# BadgeBoard.net
KiCad netlist of a schematic drawn in EAGLE
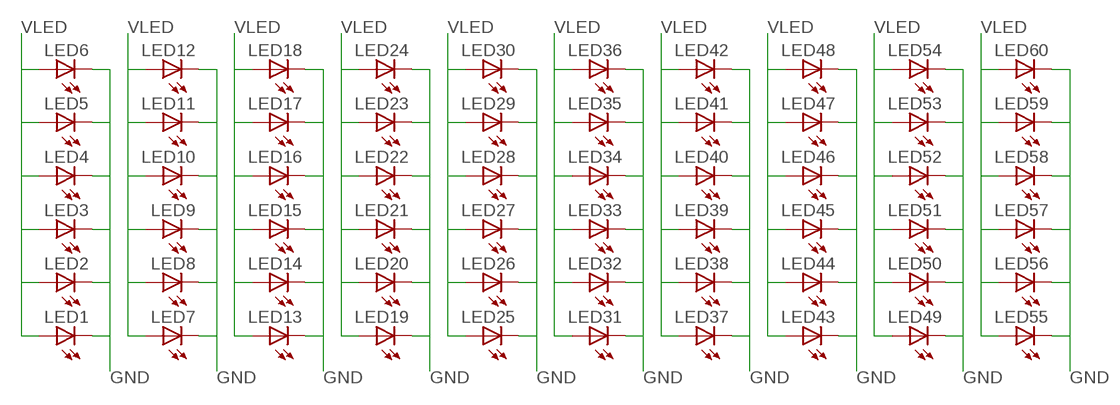
[diagram p0: schematic, sheet 1]

(export (version "E")
  (design (tool "Eeschema 10.0.6"))
  (components
    (comp (ref "LED1")
      (value "LED3MM")
      (footprint "eagle-import:LED3MM")
      (libsource (lib "eagle-import") (part "LED3MM"))
    )
    (comp (ref "LED2")
      (value "LED3MM")
      (footprint "eagle-import:LED3MM")
      (libsource (lib "eagle-import") (part "LED3MM"))
    )
    (comp (ref "LED3")
      (value "LED3MM")
      (footprint "eagle-import:LED3MM")
      (libsource (lib "eagle-import") (part "LED3MM"))
    )
    (comp (ref "LED4")
      (value "LED3MM")
      (footprint "eagle-import:LED3MM")
      (libsource (lib "eagle-import") (part "LED3MM"))
    )
    (comp (ref "LED5")
      (value "LED3MM")
      (footprint "eagle-import:LED3MM")
      (libsource (lib "eagle-import") (part "LED3MM"))
    )
    (comp (ref "LED6")
      (value "LED3MM")
      (footprint "eagle-import:LED3MM")
      (libsource (lib "eagle-import") (part "LED3MM"))
    )
    (comp (ref "LED7")
      (value "LED3MM")
      (footprint "eagle-import:LED3MM")
      (libsource (lib "eagle-import") (part "LED3MM"))
    )
    (comp (ref "LED8")
      (value "LED3MM")
      (footprint "eagle-import:LED3MM")
      (libsource (lib "eagle-import") (part "LED3MM"))
    )
    (comp (ref "LED9")
      (value "LED3MM")
      (footprint "eagle-import:LED3MM")
      (libsource (lib "eagle-import") (part "LED3MM"))
    )
    (comp (ref "LED10")
      (value "LED3MM")
      (footprint "eagle-import:LED3MM")
      (libsource (lib "eagle-import") (part "LED3MM"))
    )
    (comp (ref "LED11")
      (value "LED3MM")
      (footprint "eagle-import:LED3MM")
      (libsource (lib "eagle-import") (part "LED3MM"))
    )
    (comp (ref "LED12")
      (value "LED3MM")
      (footprint "eagle-import:LED3MM")
      (libsource (lib "eagle-import") (part "LED3MM"))
    )
    (comp (ref "LED13")
      (value "LED3MM")
      (footprint "eagle-import:LED3MM")
      (libsource (lib "eagle-import") (part "LED3MM"))
    )
    (comp (ref "LED14")
      (value "LED3MM")
      (footprint "eagle-import:LED3MM")
      (libsource (lib "eagle-import") (part "LED3MM"))
    )
    (comp (ref "LED15")
      (value "LED3MM")
      (footprint "eagle-import:LED3MM")
      (libsource (lib "eagle-import") (part "LED3MM"))
    )
    (comp (ref "LED16")
      (value "LED3MM")
      (footprint "eagle-import:LED3MM")
      (libsource (lib "eagle-import") (part "LED3MM"))
    )
    (comp (ref "LED17")
      (value "LED3MM")
      (footprint "eagle-import:LED3MM")
      (libsource (lib "eagle-import") (part "LED3MM"))
    )
    (comp (ref "LED18")
      (value "LED3MM")
      (footprint "eagle-import:LED3MM")
      (libsource (lib "eagle-import") (part "LED3MM"))
    )
    (comp (ref "LED19")
      (value "LED3MM")
      (footprint "eagle-import:LED3MM")
      (libsource (lib "eagle-import") (part "LED3MM"))
    )
    (comp (ref "LED20")
      (value "LED3MM")
      (footprint "eagle-import:LED3MM")
      (libsource (lib "eagle-import") (part "LED3MM"))
    )
    (comp (ref "LED21")
      (value "LED3MM")
      (footprint "eagle-import:LED3MM")
      (libsource (lib "eagle-import") (part "LED3MM"))
    )
    (comp (ref "LED22")
      (value "LED3MM")
      (footprint "eagle-import:LED3MM")
      (libsource (lib "eagle-import") (part "LED3MM"))
    )
    (comp (ref "LED23")
      (value "LED3MM")
      (footprint "eagle-import:LED3MM")
      (libsource (lib "eagle-import") (part "LED3MM"))
    )
    (comp (ref "LED24")
      (value "LED3MM")
      (footprint "eagle-import:LED3MM")
      (libsource (lib "eagle-import") (part "LED3MM"))
    )
    (comp (ref "LED25")
      (value "LED3MM")
      (footprint "eagle-import:LED3MM")
      (libsource (lib "eagle-import") (part "LED3MM"))
    )
    (comp (ref "LED26")
      (value "LED3MM")
      (footprint "eagle-import:LED3MM")
      (libsource (lib "eagle-import") (part "LED3MM"))
    )
    (comp (ref "LED27")
      (value "LED3MM")
      (footprint "eagle-import:LED3MM")
      (libsource (lib "eagle-import") (part "LED3MM"))
    )
    (comp (ref "LED28")
      (value "LED3MM")
      (footprint "eagle-import:LED3MM")
      (libsource (lib "eagle-import") (part "LED3MM"))
    )
    (comp (ref "LED29")
      (value "LED3MM")
      (footprint "eagle-import:LED3MM")
      (libsource (lib "eagle-import") (part "LED3MM"))
    )
    (comp (ref "LED30")
      (value "LED3MM")
      (footprint "eagle-import:LED3MM")
      (libsource (lib "eagle-import") (part "LED3MM"))
    )
    (comp (ref "LED31")
      (value "LED3MM")
      (footprint "eagle-import:LED3MM")
      (libsource (lib "eagle-import") (part "LED3MM"))
    )
    (comp (ref "LED32")
      (value "LED3MM")
      (footprint "eagle-import:LED3MM")
      (libsource (lib "eagle-import") (part "LED3MM"))
    )
    (comp (ref "LED33")
      (value "LED3MM")
      (footprint "eagle-import:LED3MM")
      (libsource (lib "eagle-import") (part "LED3MM"))
    )
    (comp (ref "LED34")
      (value "LED3MM")
      (footprint "eagle-import:LED3MM")
      (libsource (lib "eagle-import") (part "LED3MM"))
    )
    (comp (ref "LED35")
      (value "LED3MM")
      (footprint "eagle-import:LED3MM")
      (libsource (lib "eagle-import") (part "LED3MM"))
    )
    (comp (ref "LED36")
      (value "LED3MM")
      (footprint "eagle-import:LED3MM")
      (libsource (lib "eagle-import") (part "LED3MM"))
    )
    (comp (ref "LED37")
      (value "LED3MM")
      (footprint "eagle-import:LED3MM")
      (libsource (lib "eagle-import") (part "LED3MM"))
    )
    (comp (ref "LED38")
      (value "LED3MM")
      (footprint "eagle-import:LED3MM")
      (libsource (lib "eagle-import") (part "LED3MM"))
    )
    (comp (ref "LED39")
      (value "LED3MM")
      (footprint "eagle-import:LED3MM")
      (libsource (lib "eagle-import") (part "LED3MM"))
    )
    (comp (ref "LED40")
      (value "LED3MM")
      (footprint "eagle-import:LED3MM")
      (libsource (lib "eagle-import") (part "LED3MM"))
    )
    (comp (ref "LED41")
      (value "LED3MM")
      (footprint "eagle-import:LED3MM")
      (libsource (lib "eagle-import") (part "LED3MM"))
    )
    (comp (ref "LED42")
      (value "LED3MM")
      (footprint "eagle-import:LED3MM")
      (libsource (lib "eagle-import") (part "LED3MM"))
    )
    (comp (ref "LED43")
      (value "LED3MM")
      (footprint "eagle-import:LED3MM")
      (libsource (lib "eagle-import") (part "LED3MM"))
    )
    (comp (ref "LED44")
      (value "LED3MM")
      (footprint "eagle-import:LED3MM")
      (libsource (lib "eagle-import") (part "LED3MM"))
    )
    (comp (ref "LED45")
      (value "LED3MM")
      (footprint "eagle-import:LED3MM")
      (libsource (lib "eagle-import") (part "LED3MM"))
    )
    (comp (ref "LED46")
      (value "LED3MM")
      (footprint "eagle-import:LED3MM")
      (libsource (lib "eagle-import") (part "LED3MM"))
    )
    (comp (ref "LED47")
      (value "LED3MM")
      (footprint "eagle-import:LED3MM")
      (libsource (lib "eagle-import") (part "LED3MM"))
    )
    (comp (ref "LED48")
      (value "LED3MM")
      (footprint "eagle-import:LED3MM")
      (libsource (lib "eagle-import") (part "LED3MM"))
    )
    (comp (ref "LED49")
      (value "LED3MM")
      (footprint "eagle-import:LED3MM")
      (libsource (lib "eagle-import") (part "LED3MM"))
    )
    (comp (ref "LED50")
      (value "LED3MM")
      (footprint "eagle-import:LED3MM")
      (libsource (lib "eagle-import") (part "LED3MM"))
    )
    (comp (ref "LED51")
      (value "LED3MM")
      (footprint "eagle-import:LED3MM")
      (libsource (lib "eagle-import") (part "LED3MM"))
    )
    (comp (ref "LED52")
      (value "LED3MM")
      (footprint "eagle-import:LED3MM")
      (libsource (lib "eagle-import") (part "LED3MM"))
    )
    (comp (ref "LED53")
      (value "LED3MM")
      (footprint "eagle-import:LED3MM")
      (libsource (lib "eagle-import") (part "LED3MM"))
    )
    (comp (ref "LED54")
      (value "LED3MM")
      (footprint "eagle-import:LED3MM")
      (libsource (lib "eagle-import") (part "LED3MM"))
    )
    (comp (ref "LED55")
      (value "LED3MM")
      (footprint "eagle-import:LED3MM")
      (libsource (lib "eagle-import") (part "LED3MM"))
    )
    (comp (ref "LED56")
      (value "LED3MM")
      (footprint "eagle-import:LED3MM")
      (libsource (lib "eagle-import") (part "LED3MM"))
    )
    (comp (ref "LED57")
      (value "LED3MM")
      (footprint "eagle-import:LED3MM")
      (libsource (lib "eagle-import") (part "LED3MM"))
    )
    (comp (ref "LED58")
      (value "LED3MM")
      (footprint "eagle-import:LED3MM")
      (libsource (lib "eagle-import") (part "LED3MM"))
    )
    (comp (ref "LED59")
      (value "LED3MM")
      (footprint "eagle-import:LED3MM")
      (libsource (lib "eagle-import") (part "LED3MM"))
    )
    (comp (ref "LED60")
      (value "LED3MM")
      (footprint "eagle-import:LED3MM")
      (libsource (lib "eagle-import") (part "LED3MM"))
    )
  )
  (nets
    (net (code "1") (name "/GND") (class "Default")
      (node (ref "LED1") (pin "K") (pinfunction "C_K") (pintype "passive"))
      (node (ref "LED10") (pin "K") (pinfunction "C_K") (pintype "passive"))
      (node (ref "LED11") (pin "K") (pinfunction "C_K") (pintype "passive"))
      (node (ref "LED12") (pin "K") (pinfunction "C_K") (pintype "passive"))
      (node (ref "LED13") (pin "K") (pinfunction "C_K") (pintype "passive"))
      (node (ref "LED14") (pin "K") (pinfunction "C_K") (pintype "passive"))
      (node (ref "LED15") (pin "K") (pinfunction "C_K") (pintype "passive"))
      (node (ref "LED16") (pin "K") (pinfunction "C_K") (pintype "passive"))
      (node (ref "LED17") (pin "K") (pinfunction "C_K") (pintype "passive"))
      (node (ref "LED18") (pin "K") (pinfunction "C_K") (pintype "passive"))
      (node (ref "LED19") (pin "K") (pinfunction "C_K") (pintype "passive"))
      (node (ref "LED2") (pin "K") (pinfunction "C_K") (pintype "passive"))
      (node (ref "LED20") (pin "K") (pinfunction "C_K") (pintype "passive"))
      (node (ref "LED21") (pin "K") (pinfunction "C_K") (pintype "passive"))
      (node (ref "LED22") (pin "K") (pinfunction "C_K") (pintype "passive"))
      (node (ref "LED23") (pin "K") (pinfunction "C_K") (pintype "passive"))
      (node (ref "LED24") (pin "K") (pinfunction "C_K") (pintype "passive"))
      (node (ref "LED25") (pin "K") (pinfunction "C_K") (pintype "passive"))
      (node (ref "LED26") (pin "K") (pinfunction "C_K") (pintype "passive"))
      (node (ref "LED27") (pin "K") (pinfunction "C_K") (pintype "passive"))
      (node (ref "LED28") (pin "K") (pinfunction "C_K") (pintype "passive"))
      (node (ref "LED29") (pin "K") (pinfunction "C_K") (pintype "passive"))
      (node (ref "LED3") (pin "K") (pinfunction "C_K") (pintype "passive"))
      (node (ref "LED30") (pin "K") (pinfunction "C_K") (pintype "passive"))
      (node (ref "LED31") (pin "K") (pinfunction "C_K") (pintype "passive"))
      (node (ref "LED32") (pin "K") (pinfunction "C_K") (pintype "passive"))
      (node (ref "LED33") (pin "K") (pinfunction "C_K") (pintype "passive"))
      (node (ref "LED34") (pin "K") (pinfunction "C_K") (pintype "passive"))
      (node (ref "LED35") (pin "K") (pinfunction "C_K") (pintype "passive"))
      (node (ref "LED36") (pin "K") (pinfunction "C_K") (pintype "passive"))
      (node (ref "LED37") (pin "K") (pinfunction "C_K") (pintype "passive"))
      (node (ref "LED38") (pin "K") (pinfunction "C_K") (pintype "passive"))
      (node (ref "LED39") (pin "K") (pinfunction "C_K") (pintype "passive"))
      (node (ref "LED4") (pin "K") (pinfunction "C_K") (pintype "passive"))
      (node (ref "LED40") (pin "K") (pinfunction "C_K") (pintype "passive"))
      (node (ref "LED41") (pin "K") (pinfunction "C_K") (pintype "passive"))
      (node (ref "LED42") (pin "K") (pinfunction "C_K") (pintype "passive"))
      (node (ref "LED43") (pin "K") (pinfunction "C_K") (pintype "passive"))
      (node (ref "LED44") (pin "K") (pinfunction "C_K") (pintype "passive"))
      (node (ref "LED45") (pin "K") (pinfunction "C_K") (pintype "passive"))
      (node (ref "LED46") (pin "K") (pinfunction "C_K") (pintype "passive"))
      (node (ref "LED47") (pin "K") (pinfunction "C_K") (pintype "passive"))
      (node (ref "LED48") (pin "K") (pinfunction "C_K") (pintype "passive"))
      (node (ref "LED49") (pin "K") (pinfunction "C_K") (pintype "passive"))
      (node (ref "LED5") (pin "K") (pinfunction "C_K") (pintype "passive"))
      (node (ref "LED50") (pin "K") (pinfunction "C_K") (pintype "passive"))
      (node (ref "LED51") (pin "K") (pinfunction "C_K") (pintype "passive"))
      (node (ref "LED52") (pin "K") (pinfunction "C_K") (pintype "passive"))
      (node (ref "LED53") (pin "K") (pinfunction "C_K") (pintype "passive"))
      (node (ref "LED54") (pin "K") (pinfunction "C_K") (pintype "passive"))
      (node (ref "LED55") (pin "K") (pinfunction "C_K") (pintype "passive"))
      (node (ref "LED56") (pin "K") (pinfunction "C_K") (pintype "passive"))
      (node (ref "LED57") (pin "K") (pinfunction "C_K") (pintype "passive"))
      (node (ref "LED58") (pin "K") (pinfunction "C_K") (pintype "passive"))
      (node (ref "LED59") (pin "K") (pinfunction "C_K") (pintype "passive"))
      (node (ref "LED6") (pin "K") (pinfunction "C_K") (pintype "passive"))
      (node (ref "LED60") (pin "K") (pinfunction "C_K") (pintype "passive"))
      (node (ref "LED7") (pin "K") (pinfunction "C_K") (pintype "passive"))
      (node (ref "LED8") (pin "K") (pinfunction "C_K") (pintype "passive"))
      (node (ref "LED9") (pin "K") (pinfunction "C_K") (pintype "passive"))
    )
    (net (code "2") (name "/VLED") (class "Default")
      (node (ref "LED1") (pin "A") (pinfunction "A_A") (pintype "passive"))
      (node (ref "LED10") (pin "A") (pinfunction "A_A") (pintype "passive"))
      (node (ref "LED11") (pin "A") (pinfunction "A_A") (pintype "passive"))
      (node (ref "LED12") (pin "A") (pinfunction "A_A") (pintype "passive"))
      (node (ref "LED13") (pin "A") (pinfunction "A_A") (pintype "passive"))
      (node (ref "LED14") (pin "A") (pinfunction "A_A") (pintype "passive"))
      (node (ref "LED15") (pin "A") (pinfunction "A_A") (pintype "passive"))
      (node (ref "LED16") (pin "A") (pinfunction "A_A") (pintype "passive"))
      (node (ref "LED17") (pin "A") (pinfunction "A_A") (pintype "passive"))
      (node (ref "LED18") (pin "A") (pinfunction "A_A") (pintype "passive"))
      (node (ref "LED19") (pin "A") (pinfunction "A_A") (pintype "passive"))
      (node (ref "LED2") (pin "A") (pinfunction "A_A") (pintype "passive"))
      (node (ref "LED20") (pin "A") (pinfunction "A_A") (pintype "passive"))
      (node (ref "LED21") (pin "A") (pinfunction "A_A") (pintype "passive"))
      (node (ref "LED22") (pin "A") (pinfunction "A_A") (pintype "passive"))
      (node (ref "LED23") (pin "A") (pinfunction "A_A") (pintype "passive"))
      (node (ref "LED24") (pin "A") (pinfunction "A_A") (pintype "passive"))
      (node (ref "LED25") (pin "A") (pinfunction "A_A") (pintype "passive"))
      (node (ref "LED26") (pin "A") (pinfunction "A_A") (pintype "passive"))
      (node (ref "LED27") (pin "A") (pinfunction "A_A") (pintype "passive"))
      (node (ref "LED28") (pin "A") (pinfunction "A_A") (pintype "passive"))
      (node (ref "LED29") (pin "A") (pinfunction "A_A") (pintype "passive"))
      (node (ref "LED3") (pin "A") (pinfunction "A_A") (pintype "passive"))
      (node (ref "LED30") (pin "A") (pinfunction "A_A") (pintype "passive"))
      (node (ref "LED31") (pin "A") (pinfunction "A_A") (pintype "passive"))
      (node (ref "LED32") (pin "A") (pinfunction "A_A") (pintype "passive"))
      (node (ref "LED33") (pin "A") (pinfunction "A_A") (pintype "passive"))
      (node (ref "LED34") (pin "A") (pinfunction "A_A") (pintype "passive"))
      (node (ref "LED35") (pin "A") (pinfunction "A_A") (pintype "passive"))
      (node (ref "LED36") (pin "A") (pinfunction "A_A") (pintype "passive"))
      (node (ref "LED37") (pin "A") (pinfunction "A_A") (pintype "passive"))
      (node (ref "LED38") (pin "A") (pinfunction "A_A") (pintype "passive"))
      (node (ref "LED39") (pin "A") (pinfunction "A_A") (pintype "passive"))
      (node (ref "LED4") (pin "A") (pinfunction "A_A") (pintype "passive"))
      (node (ref "LED40") (pin "A") (pinfunction "A_A") (pintype "passive"))
      (node (ref "LED41") (pin "A") (pinfunction "A_A") (pintype "passive"))
      (node (ref "LED42") (pin "A") (pinfunction "A_A") (pintype "passive"))
      (node (ref "LED43") (pin "A") (pinfunction "A_A") (pintype "passive"))
      (node (ref "LED44") (pin "A") (pinfunction "A_A") (pintype "passive"))
      (node (ref "LED45") (pin "A") (pinfunction "A_A") (pintype "passive"))
      (node (ref "LED46") (pin "A") (pinfunction "A_A") (pintype "passive"))
      (node (ref "LED47") (pin "A") (pinfunction "A_A") (pintype "passive"))
      (node (ref "LED48") (pin "A") (pinfunction "A_A") (pintype "passive"))
      (node (ref "LED49") (pin "A") (pinfunction "A_A") (pintype "passive"))
      (node (ref "LED5") (pin "A") (pinfunction "A_A") (pintype "passive"))
      (node (ref "LED50") (pin "A") (pinfunction "A_A") (pintype "passive"))
      (node (ref "LED51") (pin "A") (pinfunction "A_A") (pintype "passive"))
      (node (ref "LED52") (pin "A") (pinfunction "A_A") (pintype "passive"))
      (node (ref "LED53") (pin "A") (pinfunction "A_A") (pintype "passive"))
      (node (ref "LED54") (pin "A") (pinfunction "A_A") (pintype "passive"))
      (node (ref "LED55") (pin "A") (pinfunction "A_A") (pintype "passive"))
      (node (ref "LED56") (pin "A") (pinfunction "A_A") (pintype "passive"))
      (node (ref "LED57") (pin "A") (pinfunction "A_A") (pintype "passive"))
      (node (ref "LED58") (pin "A") (pinfunction "A_A") (pintype "passive"))
      (node (ref "LED59") (pin "A") (pinfunction "A_A") (pintype "passive"))
      (node (ref "LED6") (pin "A") (pinfunction "A_A") (pintype "passive"))
      (node (ref "LED60") (pin "A") (pinfunction "A_A") (pintype "passive"))
      (node (ref "LED7") (pin "A") (pinfunction "A_A") (pintype "passive"))
      (node (ref "LED8") (pin "A") (pinfunction "A_A") (pintype "passive"))
      (node (ref "LED9") (pin "A") (pinfunction "A_A") (pintype "passive"))
    )
  )
)
